# debug.net
KiCad netlist of a schematic drawn in EAGLE
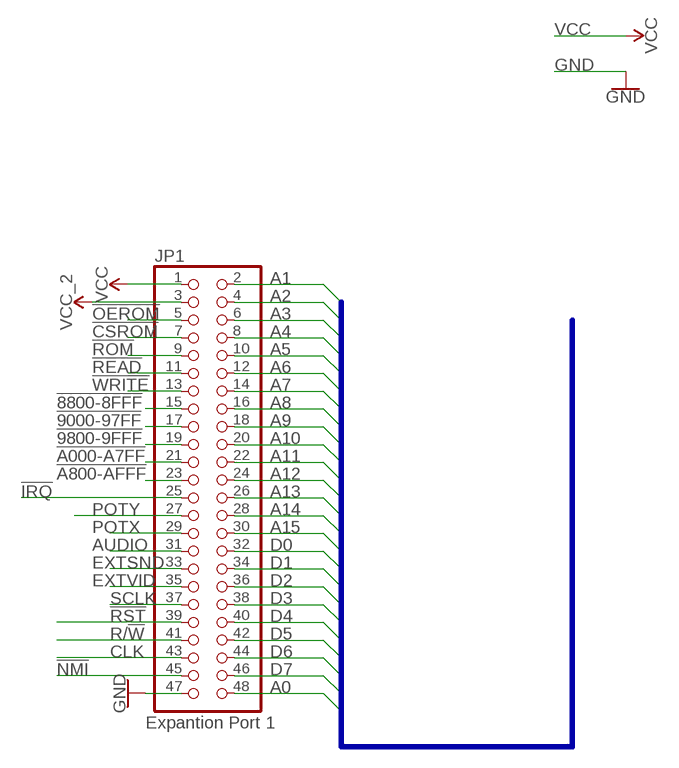
[diagram p0: schematic, sheet 1]
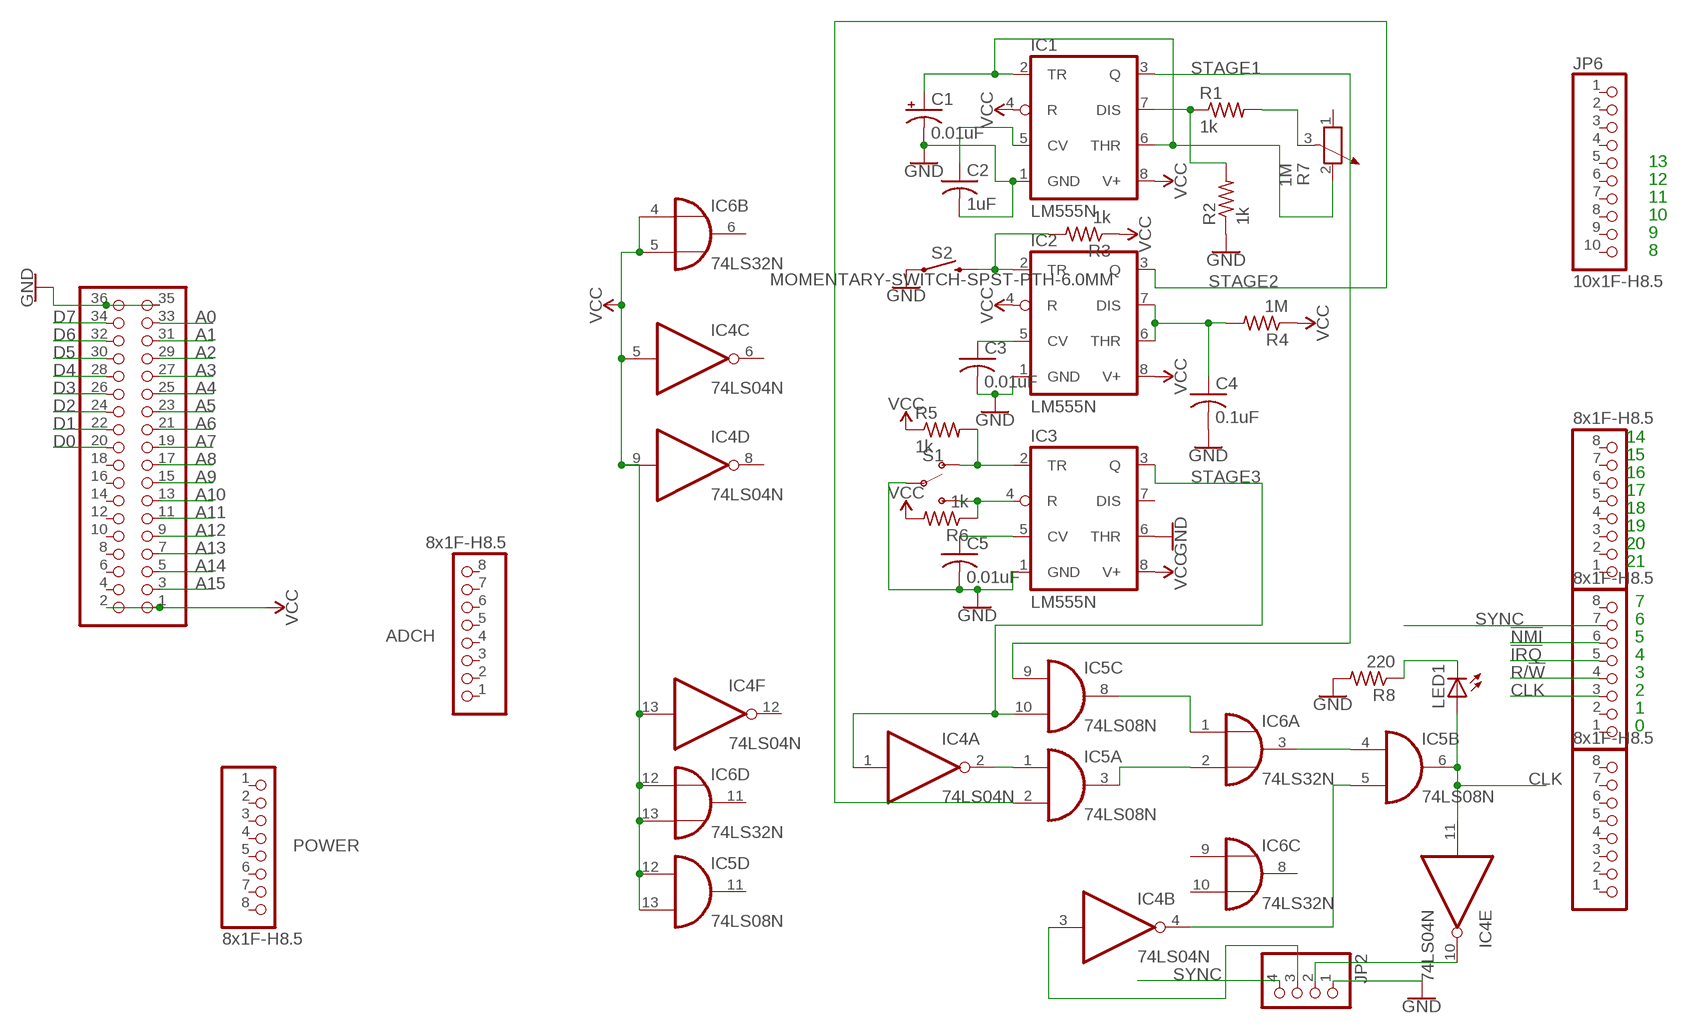
[diagram p1: schematic, sheet 2]

(export (version "E")
  (design (tool "Eeschema 10.0.6"))
  (components
    (comp (ref "JP1")
      (value "PINHD-2X24/90")
      (footprint "eagle-import:2X24_90")
      (libsource (lib "eagle-import") (part "PINHD-2X24/90"))
    )
    (comp (ref "ADCH")
      (value "8x1F-H8.5")
      (footprint "eagle-import:1X08")
      (libsource (lib "eagle-import") (part "PINHD-1X8"))
    )
    (comp (ref "ADCL")
      (value "8x1F-H8.5")
      (footprint "eagle-import:1X08")
      (libsource (lib "eagle-import") (part "PINHD-1X8"))
    )
    (comp (ref "C1")
      (value "0.01uF")
      (footprint "eagle-import:E5-10,5")
      (libsource (lib "eagle-import") (part "CPOL-USE5-10.5"))
    )
    (comp (ref "C2")
      (value "1uF")
      (footprint "eagle-import:C025-030X050")
      (libsource (lib "eagle-import") (part "C-US025-030X050"))
    )
    (comp (ref "C3")
      (value "0.01uF")
      (footprint "eagle-import:C025-030X050")
      (libsource (lib "eagle-import") (part "C-US025-030X050"))
    )
    (comp (ref "C4")
      (value "0.1uF")
      (footprint "eagle-import:C025-030X050")
      (libsource (lib "eagle-import") (part "C-US025-030X050"))
    )
    (comp (ref "C5")
      (value "0.01uF")
      (footprint "eagle-import:C025-030X050")
      (libsource (lib "eagle-import") (part "C-US025-030X050"))
    )
    (comp (ref "COMMUNICATION")
      (value "8x1F-H8.5")
      (footprint "eagle-import:1X08")
      (libsource (lib "eagle-import") (part "PINHD-1X8"))
    )
    (comp (ref "IC1")
      (value "LM555N")
      (footprint "eagle-import:DIL08-ROUND")
      (libsource (lib "eagle-import") (part "555NLM"))
    )
    (comp (ref "IC2")
      (value "LM555N")
      (footprint "eagle-import:DIL08-ROUND")
      (libsource (lib "eagle-import") (part "555NLM"))
    )
    (comp (ref "IC3")
      (value "LM555N")
      (footprint "eagle-import:DIL08-ROUND")
      (libsource (lib "eagle-import") (part "555NLM"))
    )
    (comp (ref "IC4")
      (value "74LS04N")
      (footprint "eagle-import:DIL14")
      (libsource (lib "eagle-import") (part "7404NLS"))
    )
    (comp (ref "IC5")
      (value "74LS08N")
      (footprint "eagle-import:DIL14")
      (libsource (lib "eagle-import") (part "7408NLS"))
    )
    (comp (ref "IC6")
      (value "74LS32N")
      (footprint "eagle-import:DIL14")
      (libsource (lib "eagle-import") (part "7432NLS"))
    )
    (comp (ref "JP2")
      (value "PINHD-1X4")
      (footprint "eagle-import:1X04")
      (libsource (lib "eagle-import") (part "PINHD-1X4"))
    )
    (comp (ref "JP6")
      (value "10x1F-H8.5")
      (footprint "eagle-import:1X10")
      (libsource (lib "eagle-import") (part "PINHD-1X10_ARD"))
    )
    (comp (ref "LED1")
      (value "LED5MM")
      (footprint "eagle-import:LED5MM")
      (libsource (lib "eagle-import") (part "LED5MM"))
    )
    (comp (ref "POWER")
      (value "8x1F-H8.5")
      (footprint "eagle-import:1X08")
      (libsource (lib "eagle-import") (part "PINHD-1X8"))
    )
    (comp (ref "PWML")
      (value "8x1F-H8.5")
      (footprint "eagle-import:1X08")
      (libsource (lib "eagle-import") (part "PINHD-1X8"))
    )
    (comp (ref "R1")
      (value "1k")
      (footprint "eagle-import:0204_7")
      (libsource (lib "eagle-import") (part "R-US_0204/7"))
    )
    (comp (ref "R2")
      (value "1k")
      (footprint "eagle-import:0204_7")
      (libsource (lib "eagle-import") (part "R-US_0204/7"))
    )
    (comp (ref "R3")
      (value "1k")
      (footprint "eagle-import:0204_7")
      (libsource (lib "eagle-import") (part "R-US_0204/7"))
    )
    (comp (ref "R4")
      (value "1M")
      (footprint "eagle-import:0204_7")
      (libsource (lib "eagle-import") (part "R-US_0204/7"))
    )
    (comp (ref "R5")
      (value "1k")
      (footprint "eagle-import:0204_7")
      (libsource (lib "eagle-import") (part "R-US_0204/7"))
    )
    (comp (ref "R6")
      (value "1k")
      (footprint "eagle-import:0204_7")
      (libsource (lib "eagle-import") (part "R-US_0204/7"))
    )
    (comp (ref "R7")
      (value "1M")
      (footprint "eagle-import:PT-10")
      (libsource (lib "eagle-import") (part "POTENTIOMETER_PT-10"))
    )
    (comp (ref "R8")
      (value "220")
      (footprint "eagle-import:0204_7")
      (libsource (lib "eagle-import") (part "R-US_0204/7"))
    )
    (comp (ref "S1")
      (value "SWITCH-SPDT-PTH-11.6X4.0MM-LOCK")
      (footprint "eagle-import:SWITCH_SPDT_PTH_11.6X4.0MM_LOCK")
      (libsource (lib "eagle-import") (part "SWITCH-SPDT-PTH-11.6X4.0MM-LOCK"))
    )
    (comp (ref "S2")
      (value "MOMENTARY-SWITCH-SPST-PTH-6.0MM")
      (footprint "eagle-import:TACTILE_SWITCH_PTH_6.0MM")
      (libsource (lib "eagle-import") (part "MOMENTARY-SWITCH-SPST-PTH-6.0MM"))
    )
    (comp (ref "XIO")
      (value "18x2F-H8.5")
      (footprint "eagle-import:2X18")
      (libsource (lib "eagle-import") (part "PINHD-2X18"))
    )
  )
  (nets
    (net (code "1") (name "A0") (class "Default")
      (node (ref "JP1") (pin "48") (pinfunction "48_48") (pintype "passive"))
      (node (ref "XIO") (pin "33") (pinfunction "33_33") (pintype "passive"))
    )
    (net (code "2") (name "A1") (class "Default")
      (node (ref "JP1") (pin "2") (pinfunction "2_2") (pintype "passive"))
      (node (ref "XIO") (pin "31") (pinfunction "31_31") (pintype "passive"))
    )
    (net (code "3") (name "A2") (class "Default")
      (node (ref "JP1") (pin "4") (pinfunction "4_4") (pintype "passive"))
      (node (ref "XIO") (pin "29") (pinfunction "29_29") (pintype "passive"))
    )
    (net (code "4") (name "A3") (class "Default")
      (node (ref "JP1") (pin "6") (pinfunction "6_6") (pintype "passive"))
      (node (ref "XIO") (pin "27") (pinfunction "27_27") (pintype "passive"))
    )
    (net (code "5") (name "A4") (class "Default")
      (node (ref "JP1") (pin "8") (pinfunction "8_8") (pintype "passive"))
      (node (ref "XIO") (pin "25") (pinfunction "25_25") (pintype "passive"))
    )
    (net (code "6") (name "A5") (class "Default")
      (node (ref "JP1") (pin "10") (pinfunction "10_10") (pintype "passive"))
      (node (ref "XIO") (pin "23") (pinfunction "23_23") (pintype "passive"))
    )
    (net (code "7") (name "A6") (class "Default")
      (node (ref "JP1") (pin "12") (pinfunction "12_12") (pintype "passive"))
      (node (ref "XIO") (pin "21") (pinfunction "21_21") (pintype "passive"))
    )
    (net (code "8") (name "A7") (class "Default")
      (node (ref "JP1") (pin "14") (pinfunction "14_14") (pintype "passive"))
      (node (ref "XIO") (pin "19") (pinfunction "19_19") (pintype "passive"))
    )
    (net (code "9") (name "A8") (class "Default")
      (node (ref "JP1") (pin "16") (pinfunction "16_16") (pintype "passive"))
      (node (ref "XIO") (pin "17") (pinfunction "17_17") (pintype "passive"))
    )
    (net (code "10") (name "A9") (class "Default")
      (node (ref "JP1") (pin "18") (pinfunction "18_18") (pintype "passive"))
      (node (ref "XIO") (pin "15") (pinfunction "15_15") (pintype "passive"))
    )
    (net (code "11") (name "A10") (class "Default")
      (node (ref "JP1") (pin "20") (pinfunction "20_20") (pintype "passive"))
      (node (ref "XIO") (pin "13") (pinfunction "13_13") (pintype "passive"))
    )
    (net (code "12") (name "A11") (class "Default")
      (node (ref "JP1") (pin "22") (pinfunction "22_22") (pintype "passive"))
      (node (ref "XIO") (pin "11") (pinfunction "11_11") (pintype "passive"))
    )
    (net (code "13") (name "A12") (class "Default")
      (node (ref "JP1") (pin "24") (pinfunction "24_24") (pintype "passive"))
      (node (ref "XIO") (pin "9") (pinfunction "9_9") (pintype "passive"))
    )
    (net (code "14") (name "A13") (class "Default")
      (node (ref "JP1") (pin "26") (pinfunction "26_26") (pintype "passive"))
      (node (ref "XIO") (pin "7") (pinfunction "7_7") (pintype "passive"))
    )
    (net (code "15") (name "A14") (class "Default")
      (node (ref "JP1") (pin "28") (pinfunction "28_28") (pintype "passive"))
      (node (ref "XIO") (pin "5") (pinfunction "5_5") (pintype "passive"))
    )
    (net (code "16") (name "A15") (class "Default")
      (node (ref "JP1") (pin "30") (pinfunction "30_30") (pintype "passive"))
      (node (ref "XIO") (pin "3") (pinfunction "3_3") (pintype "passive"))
    )
    (net (code "17") (name "AUDIO") (class "Default")
      (node (ref "JP1") (pin "31") (pinfunction "31_31") (pintype "passive"))
    )
    (net (code "18") (name "CLK") (class "Default")
      (node (ref "IC4") (pin "11") (pinfunction "I_11") (pintype "input"))
      (node (ref "IC5") (pin "6") (pinfunction "O_6") (pintype "output"))
      (node (ref "JP1") (pin "43") (pinfunction "43_43") (pintype "passive"))
      (node (ref "LED1") (pin "A") (pinfunction "A_A") (pintype "passive"))
      (node (ref "PWML") (pin "3") (pinfunction "3_3") (pintype "passive"))
    )
    (net (code "19") (name "D0") (class "Default")
      (node (ref "JP1") (pin "32") (pinfunction "32_32") (pintype "passive"))
      (node (ref "XIO") (pin "20") (pinfunction "20_20") (pintype "passive"))
    )
    (net (code "20") (name "D1") (class "Default")
      (node (ref "JP1") (pin "34") (pinfunction "34_34") (pintype "passive"))
      (node (ref "XIO") (pin "22") (pinfunction "22_22") (pintype "passive"))
    )
    (net (code "21") (name "D2") (class "Default")
      (node (ref "JP1") (pin "36") (pinfunction "36_36") (pintype "passive"))
      (node (ref "XIO") (pin "24") (pinfunction "24_24") (pintype "passive"))
    )
    (net (code "22") (name "D3") (class "Default")
      (node (ref "JP1") (pin "38") (pinfunction "38_38") (pintype "passive"))
      (node (ref "XIO") (pin "26") (pinfunction "26_26") (pintype "passive"))
    )
    (net (code "23") (name "D4") (class "Default")
      (node (ref "JP1") (pin "40") (pinfunction "40_40") (pintype "passive"))
      (node (ref "XIO") (pin "28") (pinfunction "28_28") (pintype "passive"))
    )
    (net (code "24") (name "D5") (class "Default")
      (node (ref "JP1") (pin "42") (pinfunction "42_42") (pintype "passive"))
      (node (ref "XIO") (pin "30") (pinfunction "30_30") (pintype "passive"))
    )
    (net (code "25") (name "D6") (class "Default")
      (node (ref "JP1") (pin "44") (pinfunction "44_44") (pintype "passive"))
      (node (ref "XIO") (pin "32") (pinfunction "32_32") (pintype "passive"))
    )
    (net (code "26") (name "D7") (class "Default")
      (node (ref "JP1") (pin "46") (pinfunction "46_46") (pintype "passive"))
      (node (ref "XIO") (pin "34") (pinfunction "34_34") (pintype "passive"))
    )
    (net (code "27") (name "EXTSND") (class "Default")
      (node (ref "JP1") (pin "33") (pinfunction "33_33") (pintype "passive"))
    )
    (net (code "28") (name "EXTVID") (class "Default")
      (node (ref "JP1") (pin "35") (pinfunction "35_35") (pintype "passive"))
    )
    (net (code "29") (name "GND") (class "Default")
      (node (ref "C1") (pin "-") (pinfunction "-_-") (pintype "passive"))
      (node (ref "C2") (pin "2") (pinfunction "2_2") (pintype "passive"))
      (node (ref "C3") (pin "2") (pinfunction "2_2") (pintype "passive"))
      (node (ref "C4") (pin "2") (pinfunction "2_2") (pintype "passive"))
      (node (ref "C5") (pin "2") (pinfunction "2_2") (pintype "passive"))
      (node (ref "IC1") (pin "1") (pinfunction "GND_1") (pintype "power_in"))
      (node (ref "IC2") (pin "1") (pinfunction "GND_1") (pintype "power_in"))
      (node (ref "IC3") (pin "1") (pinfunction "GND_1") (pintype "power_in"))
      (node (ref "IC3") (pin "6") (pinfunction "THR_6") (pintype "input"))
      (node (ref "JP1") (pin "47") (pinfunction "47_47") (pintype "passive"))
      (node (ref "JP2") (pin "1") (pinfunction "1_1") (pintype "passive"))
      (node (ref "R2") (pin "1") (pinfunction "1_1") (pintype "passive"))
      (node (ref "R8") (pin "2") (pinfunction "2_2") (pintype "passive"))
      (node (ref "S1") (pin "2") (pinfunction "P_2") (pintype "passive"))
      (node (ref "S2") (pin "1") (pinfunction "1_1") (pintype "passive"))
      (node (ref "XIO") (pin "35") (pinfunction "35_35") (pintype "passive"))
      (node (ref "XIO") (pin "36") (pinfunction "36_36") (pintype "passive"))
    )
    (net (code "30") (name "Net-(IC1-CV)") (class "Default")
      (node (ref "C2") (pin "1") (pinfunction "1_1") (pintype "passive"))
      (node (ref "IC1") (pin "5") (pinfunction "CV_5") (pintype "input"))
    )
    (net (code "31") (name "Net-(IC1-DIS)") (class "Default")
      (node (ref "IC1") (pin "7") (pinfunction "DIS_7") (pintype "input"))
      (node (ref "R1") (pin "1") (pinfunction "1_1") (pintype "passive"))
      (node (ref "R2") (pin "2") (pinfunction "2_2") (pintype "passive"))
    )
    (net (code "32") (name "Net-(IC1-THR)") (class "Default")
      (node (ref "C1") (pin "+") (pinfunction "+_+") (pintype "passive"))
      (node (ref "IC1") (pin "2") (pinfunction "TR_2") (pintype "input"))
      (node (ref "IC1") (pin "6") (pinfunction "THR_6") (pintype "input"))
      (node (ref "R7") (pin "2") (pinfunction "2_2") (pintype "passive"))
    )
    (net (code "33") (name "Net-(IC2-CV)") (class "Default")
      (node (ref "C3") (pin "1") (pinfunction "1_1") (pintype "passive"))
      (node (ref "IC2") (pin "5") (pinfunction "CV_5") (pintype "input"))
    )
    (net (code "34") (name "Net-(IC2-DIS)") (class "Default")
      (node (ref "C4") (pin "1") (pinfunction "1_1") (pintype "passive"))
      (node (ref "IC2") (pin "6") (pinfunction "THR_6") (pintype "input"))
      (node (ref "IC2") (pin "7") (pinfunction "DIS_7") (pintype "input"))
      (node (ref "R4") (pin "2") (pinfunction "2_2") (pintype "passive"))
    )
    (net (code "35") (name "Net-(IC2-TR)") (class "Default")
      (node (ref "IC2") (pin "2") (pinfunction "TR_2") (pintype "input"))
      (node (ref "R3") (pin "2") (pinfunction "2_2") (pintype "passive"))
      (node (ref "S2") (pin "3") (pinfunction "2_3") (pintype "passive"))
    )
    (net (code "36") (name "Net-(IC3-CV)") (class "Default")
      (node (ref "C5") (pin "1") (pinfunction "1_1") (pintype "passive"))
      (node (ref "IC3") (pin "5") (pinfunction "CV_5") (pintype "input"))
    )
    (net (code "37") (name "Net-(IC3-R)") (class "Default")
      (node (ref "IC3") (pin "4") (pinfunction "R_4") (pintype "input"))
      (node (ref "R6") (pin "1") (pinfunction "1_1") (pintype "passive"))
      (node (ref "S1") (pin "3") (pinfunction "S_3") (pintype "passive"))
    )
    (net (code "38") (name "Net-(IC3-TR)") (class "Default")
      (node (ref "IC3") (pin "2") (pinfunction "TR_2") (pintype "input"))
      (node (ref "R5") (pin "2") (pinfunction "2_2") (pintype "passive"))
      (node (ref "S1") (pin "1") (pinfunction "O_1") (pintype "passive"))
    )
    (net (code "39") (name "Net-(IC4A-O)") (class "Default")
      (node (ref "IC4") (pin "2") (pinfunction "O_2") (pintype "output"))
      (node (ref "IC5") (pin "1") (pinfunction "I0_1") (pintype "input"))
    )
    (net (code "40") (name "Net-(IC4B-I)") (class "Default")
      (node (ref "IC4") (pin "3") (pinfunction "I_3") (pintype "input"))
      (node (ref "JP2") (pin "3") (pinfunction "3_3") (pintype "passive"))
    )
    (net (code "41") (name "Net-(IC4B-O)") (class "Default")
      (node (ref "IC4") (pin "4") (pinfunction "O_4") (pintype "output"))
      (node (ref "IC5") (pin "5") (pinfunction "I1_5") (pintype "input"))
    )
    (net (code "42") (name "Net-(IC4E-O)") (class "Default")
      (node (ref "IC4") (pin "10") (pinfunction "O_10") (pintype "output"))
      (node (ref "JP2") (pin "2") (pinfunction "2_2") (pintype "passive"))
    )
    (net (code "43") (name "Net-(IC5A-O)") (class "Default")
      (node (ref "IC5") (pin "3") (pinfunction "O_3") (pintype "output"))
      (node (ref "IC6") (pin "2") (pinfunction "I1_2") (pintype "input"))
    )
    (net (code "44") (name "Net-(IC5B-I0)") (class "Default")
      (node (ref "IC5") (pin "4") (pinfunction "I0_4") (pintype "input"))
      (node (ref "IC6") (pin "3") (pinfunction "O_3") (pintype "output"))
    )
    (net (code "45") (name "Net-(IC5C-O)") (class "Default")
      (node (ref "IC5") (pin "8") (pinfunction "O_8") (pintype "output"))
      (node (ref "IC6") (pin "1") (pinfunction "I0_1") (pintype "input"))
    )
    (net (code "46") (name "Net-(LED1-C)") (class "Default")
      (node (ref "LED1") (pin "K") (pinfunction "C_K") (pintype "passive"))
      (node (ref "R8") (pin "1") (pinfunction "1_1") (pintype "passive"))
    )
    (net (code "47") (name "Net-(R1-Pad2)") (class "Default")
      (node (ref "R1") (pin "2") (pinfunction "2_2") (pintype "passive"))
      (node (ref "R7") (pin "3") (pinfunction "3_3") (pintype "passive"))
    )
    (net (code "48") (name "POTX") (class "Default")
      (node (ref "JP1") (pin "29") (pinfunction "29_29") (pintype "passive"))
    )
    (net (code "49") (name "POTY") (class "Default")
      (node (ref "JP1") (pin "27") (pinfunction "27_27") (pintype "passive"))
    )
    (net (code "50") (name "R{slash}~{W}") (class "Default")
      (node (ref "JP1") (pin "41") (pinfunction "41_41") (pintype "passive"))
      (node (ref "PWML") (pin "4") (pinfunction "4_4") (pintype "passive"))
    )
    (net (code "51") (name "SCLK") (class "Default")
      (node (ref "JP1") (pin "37") (pinfunction "37_37") (pintype "passive"))
    )
    (net (code "52") (name "STAGE1") (class "Default")
      (node (ref "IC1") (pin "3") (pinfunction "Q_3") (pintype "output"))
      (node (ref "IC5") (pin "9") (pinfunction "I0_9") (pintype "input"))
    )
    (net (code "53") (name "STAGE2") (class "Default")
      (node (ref "IC2") (pin "3") (pinfunction "Q_3") (pintype "output"))
      (node (ref "IC5") (pin "2") (pinfunction "I1_2") (pintype "input"))
    )
    (net (code "54") (name "STAGE3") (class "Default")
      (node (ref "IC3") (pin "3") (pinfunction "Q_3") (pintype "output"))
      (node (ref "IC4") (pin "1") (pinfunction "I_1") (pintype "input"))
      (node (ref "IC5") (pin "10") (pinfunction "I1_10") (pintype "input"))
    )
    (net (code "55") (name "SYNC") (class "Default")
      (node (ref "JP2") (pin "4") (pinfunction "4_4") (pintype "passive"))
      (node (ref "PWML") (pin "7") (pinfunction "7_7") (pintype "passive"))
    )
    (net (code "56") (name "VCC") (class "Default")
      (node (ref "IC1") (pin "4") (pinfunction "R_4") (pintype "input"))
      (node (ref "IC1") (pin "8") (pinfunction "V+_8") (pintype "power_in"))
      (node (ref "IC2") (pin "4") (pinfunction "R_4") (pintype "input"))
      (node (ref "IC2") (pin "8") (pinfunction "V+_8") (pintype "power_in"))
      (node (ref "IC3") (pin "8") (pinfunction "V+_8") (pintype "power_in"))
      (node (ref "IC4") (pin "13") (pinfunction "I_13") (pintype "input"))
      (node (ref "IC4") (pin "5") (pinfunction "I_5") (pintype "input"))
      (node (ref "IC4") (pin "9") (pinfunction "I_9") (pintype "input"))
      (node (ref "IC5") (pin "12") (pinfunction "I0_12") (pintype "input"))
      (node (ref "IC5") (pin "13") (pinfunction "I1_13") (pintype "input"))
      (node (ref "IC6") (pin "12") (pinfunction "I0_12") (pintype "input"))
      (node (ref "IC6") (pin "13") (pinfunction "I1_13") (pintype "input"))
      (node (ref "IC6") (pin "4") (pinfunction "I0_4") (pintype "input"))
      (node (ref "IC6") (pin "5") (pinfunction "I1_5") (pintype "input"))
      (node (ref "JP1") (pin "1") (pinfunction "1_1") (pintype "passive"))
      (node (ref "R3") (pin "1") (pinfunction "1_1") (pintype "passive"))
      (node (ref "R4") (pin "1") (pinfunction "1_1") (pintype "passive"))
      (node (ref "R5") (pin "1") (pinfunction "1_1") (pintype "passive"))
      (node (ref "R6") (pin "2") (pinfunction "2_2") (pintype "passive"))
      (node (ref "XIO") (pin "1") (pinfunction "1_1") (pintype "passive"))
      (node (ref "XIO") (pin "2") (pinfunction "2_2") (pintype "passive"))
    )
    (net (code "57") (name "VCC_2") (class "Default")
      (node (ref "JP1") (pin "3") (pinfunction "3_3") (pintype "passive"))
    )
    (net (code "58") (name "unconnected-(ADCH-Pad1)") (class "Default")
      (node (ref "ADCH") (pin "1") (pinfunction "1_1") (pintype "passive"))
    )
    (net (code "59") (name "unconnected-(ADCH-Pad2)") (class "Default")
      (node (ref "ADCH") (pin "2") (pinfunction "2_2") (pintype "passive"))
    )
    (net (code "60") (name "unconnected-(ADCH-Pad3)") (class "Default")
      (node (ref "ADCH") (pin "3") (pinfunction "3_3") (pintype "passive"))
    )
    (net (code "61") (name "unconnected-(ADCH-Pad4)") (class "Default")
      (node (ref "ADCH") (pin "4") (pinfunction "4_4") (pintype "passive"))
    )
    (net (code "62") (name "unconnected-(ADCH-Pad5)") (class "Default")
      (node (ref "ADCH") (pin "5") (pinfunction "5_5") (pintype "passive"))
    )
    (net (code "63") (name "unconnected-(ADCH-Pad6)") (class "Default")
      (node (ref "ADCH") (pin "6") (pinfunction "6_6") (pintype "passive"))
    )
    (net (code "64") (name "unconnected-(ADCH-Pad7)") (class "Default")
      (node (ref "ADCH") (pin "7") (pinfunction "7_7") (pintype "passive"))
    )
    (net (code "65") (name "unconnected-(ADCH-Pad8)") (class "Default")
      (node (ref "ADCH") (pin "8") (pinfunction "8_8") (pintype "passive"))
    )
    (net (code "66") (name "unconnected-(ADCL-Pad1)") (class "Default")
      (node (ref "ADCL") (pin "1") (pinfunction "1_1") (pintype "passive"))
    )
    (net (code "67") (name "unconnected-(ADCL-Pad2)") (class "Default")
      (node (ref "ADCL") (pin "2") (pinfunction "2_2") (pintype "passive"))
    )
    (net (code "68") (name "unconnected-(ADCL-Pad3)") (class "Default")
      (node (ref "ADCL") (pin "3") (pinfunction "3_3") (pintype "passive"))
    )
    (net (code "69") (name "unconnected-(ADCL-Pad4)") (class "Default")
      (node (ref "ADCL") (pin "4") (pinfunction "4_4") (pintype "passive"))
    )
    (net (code "70") (name "unconnected-(ADCL-Pad5)") (class "Default")
      (node (ref "ADCL") (pin "5") (pinfunction "5_5") (pintype "passive"))
    )
    (net (code "71") (name "unconnected-(ADCL-Pad6)") (class "Default")
      (node (ref "ADCL") (pin "6") (pinfunction "6_6") (pintype "passive"))
    )
    (net (code "72") (name "unconnected-(ADCL-Pad7)") (class "Default")
      (node (ref "ADCL") (pin "7") (pinfunction "7_7") (pintype "passive"))
    )
    (net (code "73") (name "unconnected-(ADCL-Pad8)") (class "Default")
      (node (ref "ADCL") (pin "8") (pinfunction "8_8") (pintype "passive"))
    )
    (net (code "74") (name "unconnected-(COMMUNICATION-Pad1)") (class "Default")
      (node (ref "COMMUNICATION") (pin "1") (pinfunction "1_1") (pintype "passive"))
    )
    (net (code "75") (name "unconnected-(COMMUNICATION-Pad2)") (class "Default")
      (node (ref "COMMUNICATION") (pin "2") (pinfunction "2_2") (pintype "passive"))
    )
    (net (code "76") (name "unconnected-(COMMUNICATION-Pad3)") (class "Default")
      (node (ref "COMMUNICATION") (pin "3") (pinfunction "3_3") (pintype "passive"))
    )
    (net (code "77") (name "unconnected-(COMMUNICATION-Pad4)") (class "Default")
      (node (ref "COMMUNICATION") (pin "4") (pinfunction "4_4") (pintype "passive"))
    )
    (net (code "78") (name "unconnected-(COMMUNICATION-Pad5)") (class "Default")
      (node (ref "COMMUNICATION") (pin "5") (pinfunction "5_5") (pintype "passive"))
    )
    (net (code "79") (name "unconnected-(COMMUNICATION-Pad6)") (class "Default")
      (node (ref "COMMUNICATION") (pin "6") (pinfunction "6_6") (pintype "passive"))
    )
    (net (code "80") (name "unconnected-(COMMUNICATION-Pad7)") (class "Default")
      (node (ref "COMMUNICATION") (pin "7") (pinfunction "7_7") (pintype "passive"))
    )
    (net (code "81") (name "unconnected-(COMMUNICATION-Pad8)") (class "Default")
      (node (ref "COMMUNICATION") (pin "8") (pinfunction "8_8") (pintype "passive"))
    )
    (net (code "82") (name "unconnected-(IC3-DIS-Pad7)") (class "Default")
      (node (ref "IC3") (pin "7") (pinfunction "DIS_7") (pintype "input"))
    )
    (net (code "83") (name "unconnected-(IC4C-O-Pad6)") (class "Default")
      (node (ref "IC4") (pin "6") (pinfunction "O_6") (pintype "output"))
    )
    (net (code "84") (name "unconnected-(IC4D-O-Pad8)") (class "Default")
      (node (ref "IC4") (pin "8") (pinfunction "O_8") (pintype "output"))
    )
    (net (code "85") (name "unconnected-(IC4F-O-Pad12)") (class "Default")
      (node (ref "IC4") (pin "12") (pinfunction "O_12") (pintype "output"))
    )
    (net (code "86") (name "unconnected-(IC5D-O-Pad11)") (class "Default")
      (node (ref "IC5") (pin "11") (pinfunction "O_11") (pintype "output"))
    )
    (net (code "87") (name "unconnected-(IC6B-O-Pad6)") (class "Default")
      (node (ref "IC6") (pin "6") (pinfunction "O_6") (pintype "output"))
    )
    (net (code "88") (name "unconnected-(IC6C-I0-Pad9)") (class "Default")
      (node (ref "IC6") (pin "9") (pinfunction "I0_9") (pintype "input"))
    )
    (net (code "89") (name "unconnected-(IC6C-I1-Pad10)") (class "Default")
      (node (ref "IC6") (pin "10") (pinfunction "I1_10") (pintype "input"))
    )
    (net (code "90") (name "unconnected-(IC6C-O-Pad8)") (class "Default")
      (node (ref "IC6") (pin "8") (pinfunction "O_8") (pintype "output"))
    )
    (net (code "91") (name "unconnected-(IC6D-O-Pad11)") (class "Default")
      (node (ref "IC6") (pin "11") (pinfunction "O_11") (pintype "output"))
    )
    (net (code "92") (name "unconnected-(JP6-Pad1)") (class "Default")
      (node (ref "JP6") (pin "1") (pinfunction "1_1") (pintype "passive"))
    )
    (net (code "93") (name "unconnected-(JP6-Pad2)") (class "Default")
      (node (ref "JP6") (pin "2") (pinfunction "2_2") (pintype "passive"))
    )
    (net (code "94") (name "unconnected-(JP6-Pad3)") (class "Default")
      (node (ref "JP6") (pin "3") (pinfunction "3_3") (pintype "passive"))
    )
    (net (code "95") (name "unconnected-(JP6-Pad4)") (class "Default")
      (node (ref "JP6") (pin "4") (pinfunction "4_4") (pintype "passive"))
    )
    (net (code "96") (name "unconnected-(JP6-Pad5)") (class "Default")
      (node (ref "JP6") (pin "5") (pinfunction "5_5") (pintype "passive"))
    )
    (net (code "97") (name "unconnected-(JP6-Pad6)") (class "Default")
      (node (ref "JP6") (pin "6") (pinfunction "6_6") (pintype "passive"))
    )
    (net (code "98") (name "unconnected-(JP6-Pad7)") (class "Default")
      (node (ref "JP6") (pin "7") (pinfunction "7_7") (pintype "passive"))
    )
    (net (code "99") (name "unconnected-(JP6-Pad8)") (class "Default")
      (node (ref "JP6") (pin "8") (pinfunction "8_8") (pintype "passive"))
    )
    (net (code "100") (name "unconnected-(JP6-Pad9)") (class "Default")
      (node (ref "JP6") (pin "9") (pinfunction "9_9") (pintype "passive"))
    )
    (net (code "101") (name "unconnected-(JP6-Pad10)") (class "Default")
      (node (ref "JP6") (pin "10") (pinfunction "10_10") (pintype "passive"))
    )
    (net (code "102") (name "unconnected-(POWER-Pad1)") (class "Default")
      (node (ref "POWER") (pin "1") (pinfunction "1_1") (pintype "passive"))
    )
    (net (code "103") (name "unconnected-(POWER-Pad2)") (class "Default")
      (node (ref "POWER") (pin "2") (pinfunction "2_2") (pintype "passive"))
    )
    (net (code "104") (name "unconnected-(POWER-Pad3)") (class "Default")
      (node (ref "POWER") (pin "3") (pinfunction "3_3") (pintype "passive"))
    )
    (net (code "105") (name "unconnected-(POWER-Pad4)") (class "Default")
      (node (ref "POWER") (pin "4") (pinfunction "4_4") (pintype "passive"))
    )
    (net (code "106") (name "unconnected-(POWER-Pad5)") (class "Default")
      (node (ref "POWER") (pin "5") (pinfunction "5_5") (pintype "passive"))
    )
    (net (code "107") (name "unconnected-(POWER-Pad6)") (class "Default")
      (node (ref "POWER") (pin "6") (pinfunction "6_6") (pintype "passive"))
    )
    (net (code "108") (name "unconnected-(POWER-Pad7)") (class "Default")
      (node (ref "POWER") (pin "7") (pinfunction "7_7") (pintype "passive"))
    )
    (net (code "109") (name "unconnected-(POWER-Pad8)") (class "Default")
      (node (ref "POWER") (pin "8") (pinfunction "8_8") (pintype "passive"))
    )
    (net (code "110") (name "unconnected-(PWML-Pad1)") (class "Default")
      (node (ref "PWML") (pin "1") (pinfunction "1_1") (pintype "passive"))
    )
    (net (code "111") (name "unconnected-(PWML-Pad2)") (class "Default")
      (node (ref "PWML") (pin "2") (pinfunction "2_2") (pintype "passive"))
    )
    (net (code "112") (name "unconnected-(PWML-Pad8)") (class "Default")
      (node (ref "PWML") (pin "8") (pinfunction "8_8") (pintype "passive"))
    )
    (net (code "113") (name "unconnected-(R7-Pad1)") (class "Default")
      (node (ref "R7") (pin "1") (pinfunction "1_1") (pintype "passive"))
    )
    (net (code "114") (name "unconnected-(XIO-Pad4)") (class "Default")
      (node (ref "XIO") (pin "4") (pinfunction "4_4") (pintype "passive"))
    )
    (net (code "115") (name "unconnected-(XIO-Pad6)") (class "Default")
      (node (ref "XIO") (pin "6") (pinfunction "6_6") (pintype "passive"))
    )
    (net (code "116") (name "unconnected-(XIO-Pad8)") (class "Default")
      (node (ref "XIO") (pin "8") (pinfunction "8_8") (pintype "passive"))
    )
    (net (code "117") (name "unconnected-(XIO-Pad10)") (class "Default")
      (node (ref "XIO") (pin "10") (pinfunction "10_10") (pintype "passive"))
    )
    (net (code "118") (name "unconnected-(XIO-Pad12)") (class "Default")
      (node (ref "XIO") (pin "12") (pinfunction "12_12") (pintype "passive"))
    )
    (net (code "119") (name "unconnected-(XIO-Pad14)") (class "Default")
      (node (ref "XIO") (pin "14") (pinfunction "14_14") (pintype "passive"))
    )
    (net (code "120") (name "unconnected-(XIO-Pad16)") (class "Default")
      (node (ref "XIO") (pin "16") (pinfunction "16_16") (pintype "passive"))
    )
    (net (code "121") (name "unconnected-(XIO-Pad18)") (class "Default")
      (node (ref "XIO") (pin "18") (pinfunction "18_18") (pintype "passive"))
    )
    (net (code "122") (name "~{8800-8FFF}") (class "Default")
      (node (ref "JP1") (pin "15") (pinfunction "15_15") (pintype "passive"))
    )
    (net (code "123") (name "~{9000-97FF}") (class "Default")
      (node (ref "JP1") (pin "17") (pinfunction "17_17") (pintype "passive"))
    )
    (net (code "124") (name "~{9800-9FFF}") (class "Default")
      (node (ref "JP1") (pin "19") (pinfunction "19_19") (pintype "passive"))
    )
    (net (code "125") (name "~{A000-A7FF}") (class "Default")
      (node (ref "JP1") (pin "21") (pinfunction "21_21") (pintype "passive"))
    )
    (net (code "126") (name "~{A800-AFFF}") (class "Default")
      (node (ref "JP1") (pin "23") (pinfunction "23_23") (pintype "passive"))
    )
    (net (code "127") (name "~{CSROM}") (class "Default")
      (node (ref "JP1") (pin "7") (pinfunction "7_7") (pintype "passive"))
    )
    (net (code "128") (name "~{IRQ}") (class "Default")
      (node (ref "JP1") (pin "25") (pinfunction "25_25") (pintype "passive"))
      (node (ref "PWML") (pin "5") (pinfunction "5_5") (pintype "passive"))
    )
    (net (code "129") (name "~{NMI}") (class "Default")
      (node (ref "JP1") (pin "45") (pinfunction "45_45") (pintype "passive"))
      (node (ref "PWML") (pin "6") (pinfunction "6_6") (pintype "passive"))
    )
    (net (code "130") (name "~{OEROM}") (class "Default")
      (node (ref "JP1") (pin "5") (pinfunction "5_5") (pintype "passive"))
    )
    (net (code "131") (name "~{READ}") (class "Default")
      (node (ref "JP1") (pin "11") (pinfunction "11_11") (pintype "passive"))
    )
    (net (code "132") (name "~{ROM}") (class "Default")
      (node (ref "JP1") (pin "9") (pinfunction "9_9") (pintype "passive"))
    )
    (net (code "133") (name "~{RST}") (class "Default")
      (node (ref "JP1") (pin "39") (pinfunction "39_39") (pintype "passive"))
    )
    (net (code "134") (name "~{WRITE}") (class "Default")
      (node (ref "JP1") (pin "13") (pinfunction "13_13") (pintype "passive"))
    )
  )
)
